# tick-controller-mk-3.net
KiCad netlist of a schematic drawn in EAGLE
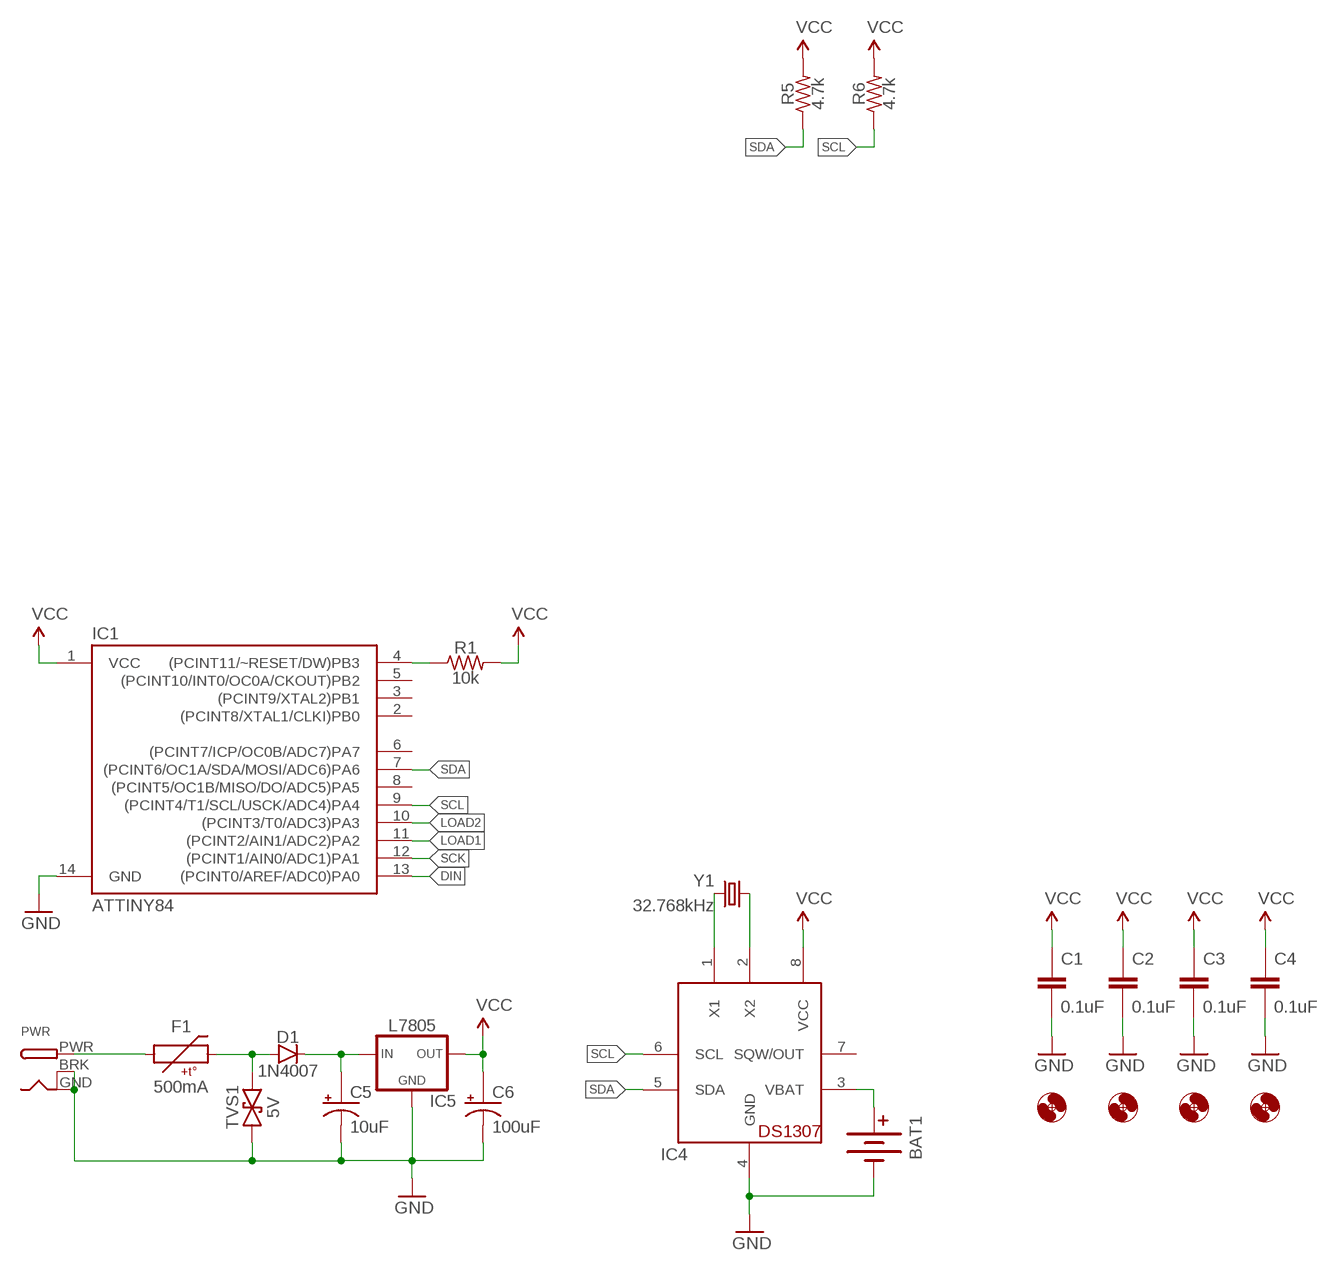
[diagram p0: schematic, sheet 1]

(export (version "E")
  (design (tool "Eeschema 10.0.6"))
  (components
    (comp (ref "BAT1")
      (value "BATTERY20SMD")
      (footprint "eagle-import:BATTCON_20MM")
      (libsource (lib "eagle-import") (part "BATTERY20SMD"))
    )
    (comp (ref "C1")
      (value "0.1uF")
      (footprint "eagle-import:C025-024X044")
      (libsource (lib "eagle-import") (part "CAPACITOR-CERAMIC025-024X044"))
    )
    (comp (ref "C2")
      (value "0.1uF")
      (footprint "eagle-import:C025-024X044")
      (libsource (lib "eagle-import") (part "CAPACITOR-CERAMIC025-024X044"))
    )
    (comp (ref "C3")
      (value "0.1uF")
      (footprint "eagle-import:C025-024X044")
      (libsource (lib "eagle-import") (part "CAPACITOR-CERAMIC025-024X044"))
    )
    (comp (ref "C4")
      (value "0.1uF")
      (footprint "eagle-import:C025-024X044")
      (libsource (lib "eagle-import") (part "CAPACITOR-CERAMIC025-024X044"))
    )
    (comp (ref "C5")
      (value "10uF")
      (footprint "eagle-import:E2-5")
      (libsource (lib "eagle-import") (part "CAPACITOR-POLARIZEDE2-5"))
    )
    (comp (ref "C6")
      (value "100uF")
      (footprint "eagle-import:E2-5")
      (libsource (lib "eagle-import") (part "CAPACITOR-POLARIZEDE2-5"))
    )
    (comp (ref "D1")
      (value "1N4007")
      (footprint "eagle-import:DIODE-10.16MM")
      (libsource (lib "eagle-import") (part "DIODEPTH-10.68MM"))
    )
    (comp (ref "F1")
      (value "500mA")
      (footprint "eagle-import:PTC-PTH-5.08MM")
      (libsource (lib "eagle-import") (part "PTCPTH-5.08MM"))
    )
    (comp (ref "H1")
      (value "HOLE#2")
      (footprint "eagle-import:HOLE-#2")
      (libsource (lib "eagle-import") (part "HOLE#2"))
    )
    (comp (ref "H2")
      (value "HOLE#2")
      (footprint "eagle-import:HOLE-#2")
      (libsource (lib "eagle-import") (part "HOLE#2"))
    )
    (comp (ref "H3")
      (value "HOLE#2")
      (footprint "eagle-import:HOLE-#2")
      (libsource (lib "eagle-import") (part "HOLE#2"))
    )
    (comp (ref "H4")
      (value "HOLE#2")
      (footprint "eagle-import:HOLE-#2")
      (libsource (lib "eagle-import") (part "HOLE#2"))
    )
    (comp (ref "IC1")
      (value "ATTINY84")
      (footprint "eagle-import:DIL14")
      (libsource (lib "eagle-import") (part "ATTINY84ATTINY84-20PU"))
    )
    (comp (ref "IC4")
      (value "DS1307")
      (footprint "eagle-import:DIL08")
      (libsource (lib "eagle-import") (part "DS1307"))
    )
    (comp (ref "IC5")
      (value "L7805")
      (footprint "eagle-import:TO-92-AMMO")
      (libsource (lib "eagle-import") (part "V_REG_78XXTO-92-INLINE"))
    )
    (comp (ref "PWR")
      (value "DCBARRELPTH")
      (footprint "eagle-import:DCJACK_2MM_PTH")
      (libsource (lib "eagle-import") (part "DCBARRELPTH"))
    )
    (comp (ref "R1")
      (value "10k")
      (footprint "eagle-import:RESISTOR-AXIAL-PTH-5.08MM")
      (libsource (lib "eagle-import") (part "RESISTORPTH-AXIAL-5.08MM"))
    )
    (comp (ref "R5")
      (value "4.7k")
      (footprint "eagle-import:RESISTOR-AXIAL-PTH-5.08MM")
      (libsource (lib "eagle-import") (part "RESISTORPTH-AXIAL-5.08MM"))
    )
    (comp (ref "R6")
      (value "4.7k")
      (footprint "eagle-import:RESISTOR-AXIAL-PTH-5.08MM")
      (libsource (lib "eagle-import") (part "RESISTORPTH-AXIAL-5.08MM"))
    )
    (comp (ref "TVS1")
      (value "5V")
      (footprint "eagle-import:DO-41-TVS-BI-10.16MM")
      (libsource (lib "eagle-import") (part "TVSDO-41-10.16MM"))
    )
    (comp (ref "Y1")
      (value "32.768kHz")
      (footprint "eagle-import:TC26H")
      (libsource (lib "eagle-import") (part "CRYSTALTC26H"))
    )
  )
  (nets
    (net (code "1") (name "DIN") (class "Default")
      (node (ref "IC1") (pin "13") (pinfunction "(PCINT0/AREF/ADC0)PA0_13") (pintype "bidirectional"))
    )
    (net (code "2") (name "GND") (class "Default")
      (node (ref "BAT1") (pin "2") (pinfunction "-_2") (pintype "power_in"))
      (node (ref "C1") (pin "2") (pinfunction "2_2") (pintype "passive"))
      (node (ref "C2") (pin "2") (pinfunction "2_2") (pintype "passive"))
      (node (ref "C3") (pin "2") (pinfunction "2_2") (pintype "passive"))
      (node (ref "C4") (pin "2") (pinfunction "2_2") (pintype "passive"))
      (node (ref "C5") (pin "-") (pinfunction "-_-") (pintype "passive"))
      (node (ref "C6") (pin "-") (pinfunction "-_-") (pintype "passive"))
      (node (ref "IC1") (pin "14") (pinfunction "GND_14") (pintype "bidirectional"))
      (node (ref "IC4") (pin "4") (pinfunction "GND_4") (pintype "power_in"))
      (node (ref "IC5") (pin "2") (pinfunction "GND_2") (pintype "input"))
      (node (ref "PWR") (pin "BRK") (pinfunction "BRK_BRK") (pintype "power_in"))
      (node (ref "PWR") (pin "GND") (pinfunction "GND_GND") (pintype "power_in"))
      (node (ref "TVS1") (pin "P$1") (pinfunction "1_P$1") (pintype "passive"))
    )
    (net (code "3") (name "LOAD1") (class "Default")
      (node (ref "IC1") (pin "11") (pinfunction "(PCINT2/AIN1/ADC2)PA2_11") (pintype "bidirectional"))
    )
    (net (code "4") (name "LOAD2") (class "Default")
      (node (ref "IC1") (pin "10") (pinfunction "(PCINT3/T0/ADC3)PA3_10") (pintype "bidirectional"))
    )
    (net (code "5") (name "Net-(F1-1)") (class "Default")
      (node (ref "F1") (pin "P$1") (pinfunction "1_P$1") (pintype "passive"))
      (node (ref "PWR") (pin "PWR") (pinfunction "PWR_PWR") (pintype "power_in"))
    )
    (net (code "6") (name "Net-(F1-2)") (class "Default")
      (node (ref "D1") (pin "A") (pinfunction "A_A") (pintype "passive"))
      (node (ref "F1") (pin "P$2") (pinfunction "2_P$2") (pintype "passive"))
      (node (ref "TVS1") (pin "P$2") (pinfunction "2_P$2") (pintype "passive"))
    )
    (net (code "7") (name "Net-(IC1-(PCINT11{slash}~{RESET{slash}DW})PB3)") (class "Default")
      (node (ref "IC1") (pin "4") (pinfunction "(PCINT11/~{RESET/DW})PB3_4") (pintype "bidirectional"))
      (node (ref "R1") (pin "P$1") (pinfunction "1_P$1") (pintype "passive"))
    )
    (net (code "8") (name "Net-(IC4-VBAT)") (class "Default")
      (node (ref "BAT1") (pin "1") (pinfunction "+_1") (pintype "power_in"))
      (node (ref "BAT1") (pin "3") (pinfunction "+_3") (pintype "power_in"))
      (node (ref "IC4") (pin "3") (pinfunction "VBAT_3") (pintype "power_in"))
    )
    (net (code "9") (name "Net-(IC4-X1)") (class "Default")
      (node (ref "IC4") (pin "1") (pinfunction "X1_1") (pintype "passive"))
      (node (ref "Y1") (pin "2") (pinfunction "2_2") (pintype "passive"))
    )
    (net (code "10") (name "Net-(IC4-X2)") (class "Default")
      (node (ref "IC4") (pin "2") (pinfunction "X2_2") (pintype "passive"))
      (node (ref "Y1") (pin "1") (pinfunction "1_1") (pintype "passive"))
    )
    (net (code "11") (name "Net-(IC5-IN)") (class "Default")
      (node (ref "C5") (pin "+") (pinfunction "+_+") (pintype "passive"))
      (node (ref "D1") (pin "C") (pinfunction "C_C") (pintype "passive"))
      (node (ref "IC5") (pin "1") (pinfunction "IN_1") (pintype "input"))
    )
    (net (code "12") (name "SCK") (class "Default")
      (node (ref "IC1") (pin "12") (pinfunction "(PCINT1/AIN0/ADC1)PA1_12") (pintype "bidirectional"))
    )
    (net (code "13") (name "SCL") (class "Default")
      (node (ref "IC1") (pin "9") (pinfunction "(PCINT4/T1/SCL/USCK/ADC4)PA4_9") (pintype "bidirectional"))
      (node (ref "IC4") (pin "6") (pinfunction "SCL_6") (pintype "bidirectional"))
      (node (ref "R6") (pin "P$1") (pinfunction "1_P$1") (pintype "passive"))
    )
    (net (code "14") (name "SDA") (class "Default")
      (node (ref "IC1") (pin "7") (pinfunction "(PCINT6/OC1A/SDA/MOSI/ADC6)PA6_7") (pintype "bidirectional"))
      (node (ref "IC4") (pin "5") (pinfunction "SDA_5") (pintype "bidirectional"))
      (node (ref "R5") (pin "P$1") (pinfunction "1_P$1") (pintype "passive"))
    )
    (net (code "15") (name "VCC") (class "Default")
      (node (ref "C1") (pin "1") (pinfunction "1_1") (pintype "passive"))
      (node (ref "C2") (pin "1") (pinfunction "1_1") (pintype "passive"))
      (node (ref "C3") (pin "1") (pinfunction "1_1") (pintype "passive"))
      (node (ref "C4") (pin "1") (pinfunction "1_1") (pintype "passive"))
      (node (ref "C6") (pin "+") (pinfunction "+_+") (pintype "passive"))
      (node (ref "IC1") (pin "1") (pinfunction "VCC_1") (pintype "bidirectional"))
      (node (ref "IC4") (pin "8") (pinfunction "VCC_8") (pintype "power_in"))
      (node (ref "IC5") (pin "3") (pinfunction "OUT_3") (pintype "output"))
      (node (ref "R1") (pin "P$2") (pinfunction "2_P$2") (pintype "passive"))
      (node (ref "R5") (pin "P$2") (pinfunction "2_P$2") (pintype "passive"))
      (node (ref "R6") (pin "P$2") (pinfunction "2_P$2") (pintype "passive"))
    )
    (net (code "16") (name "unconnected-(IC1-(PCINT5{slash}OC1B{slash}MISO{slash}DO{slash}ADC5)PA5-Pad8)") (class "Default")
      (node (ref "IC1") (pin "8") (pinfunction "(PCINT5/OC1B/MISO/DO/ADC5)PA5_8") (pintype "bidirectional"))
    )
    (net (code "17") (name "unconnected-(IC1-(PCINT7{slash}ICP{slash}OC0B{slash}ADC7)PA7-Pad6)") (class "Default")
      (node (ref "IC1") (pin "6") (pinfunction "(PCINT7/ICP/OC0B/ADC7)PA7_6") (pintype "bidirectional"))
    )
    (net (code "18") (name "unconnected-(IC1-(PCINT8{slash}XTAL1{slash}CLKI)PB0-Pad2)") (class "Default")
      (node (ref "IC1") (pin "2") (pinfunction "(PCINT8/XTAL1/CLKI)PB0_2") (pintype "bidirectional"))
    )
    (net (code "19") (name "unconnected-(IC1-(PCINT9{slash}XTAL2)PB1-Pad3)") (class "Default")
      (node (ref "IC1") (pin "3") (pinfunction "(PCINT9/XTAL2)PB1_3") (pintype "bidirectional"))
    )
    (net (code "20") (name "unconnected-(IC1-(PCINT10{slash}INT0{slash}OC0A{slash}CKOUT)PB2-Pad5)") (class "Default")
      (node (ref "IC1") (pin "5") (pinfunction "(PCINT10/INT0/OC0A/CKOUT)PB2_5") (pintype "bidirectional"))
    )
    (net (code "21") (name "unconnected-(IC4-SQW{slash}OUT-Pad7)") (class "Default")
      (node (ref "IC4") (pin "7") (pinfunction "SQW/OUT_7") (pintype "bidirectional"))
    )
  )
)
